# Motor.net
KiCad netlist of a schematic drawn in Altium Designer
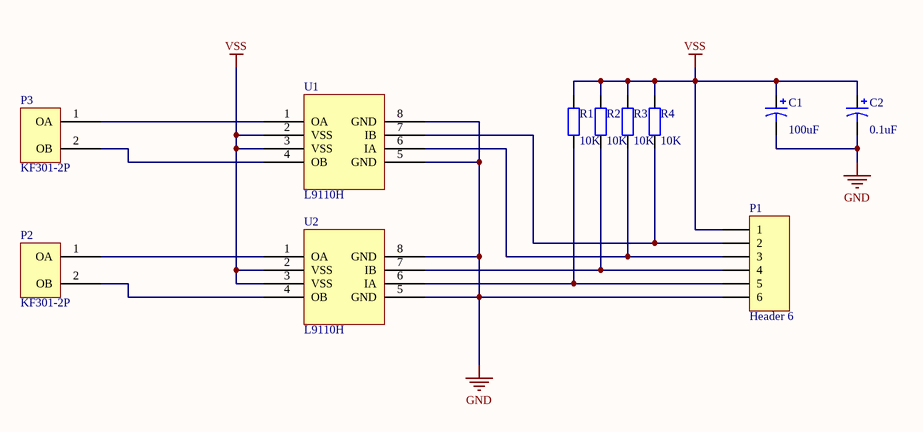
[diagram p0: Motor.SchDoc]

(export (version "E")
  (design (tool "Eeschema 10.0.6"))
  (components
    (comp (ref "C1")
      (value "100uF")
      (footprint "RB7.6-15")
      (description "Polarized Capacitor (Radial)")
      (fields (field (name "Comment") "Cap Pol1") (field (name "PUBLISHER") "Altium Limited"))
      (libsource (lib "Miscellaneous Devices") (part "Cap Pol1"))
    )
    (comp (ref "C2")
      (value "0.1uF")
      (footprint "RB7.6-15")
      (description "Polarized Capacitor (Radial)")
      (fields (field (name "Comment") "Cap Pol1") (field (name "PUBLISHER") "Altium Limited"))
      (libsource (lib "Miscellaneous Devices") (part "Cap Pol1"))
    )
    (comp (ref "P1")
      (value "Header 6")
      (footprint "HDR1X6")
      (description "Header, 6-Pin")
      (fields (field (name "PUBLISHER") "Altium Limited"))
      (libsource (lib "Miscellaneous Connectors") (part "Header 6"))
    )
    (comp (ref "P2") (value "KF301-2P") (footprint "DIP2") (libsource (lib "Motor") (part "KF301-2P")))
    (comp (ref "P3") (value "KF301-2P") (footprint "DIP2") (libsource (lib "Motor") (part "KF301-2P")))
    (comp (ref "R1")
      (value "10K")
      (footprint "AXIAL-0.4")
      (description "Resistor")
      (fields (field (name "Comment") "Res2") (field (name "PUBLISHER") "Altium Limited"))
      (libsource (lib "Miscellaneous Devices") (part "Res2"))
    )
    (comp (ref "R2")
      (value "10K")
      (footprint "AXIAL-0.4")
      (description "Resistor")
      (fields (field (name "Comment") "Res2") (field (name "PUBLISHER") "Altium Limited"))
      (libsource (lib "Miscellaneous Devices") (part "Res2"))
    )
    (comp (ref "R3")
      (value "10K")
      (footprint "AXIAL-0.4")
      (description "Resistor")
      (fields (field (name "Comment") "Res2") (field (name "PUBLISHER") "Altium Limited"))
      (libsource (lib "Miscellaneous Devices") (part "Res2"))
    )
    (comp (ref "R4")
      (value "10K")
      (footprint "AXIAL-0.4")
      (description "Resistor")
      (fields (field (name "Comment") "Res2") (field (name "PUBLISHER") "Altium Limited"))
      (libsource (lib "Miscellaneous Devices") (part "Res2"))
    )
    (comp (ref "U1") (value "L9110H") (footprint "Motor:DIP8") (libsource (lib "Motor") (part "L9110H")))
    (comp (ref "U2") (value "L9110H") (footprint "Motor:DIP8") (libsource (lib "Motor") (part "L9110H")))
  )
  (nets
    (net (code "1") (name "GND") (class "Default")
      (node (ref "C1") (pin "2") (pinfunction "2_2") (pintype "passive"))
      (node (ref "C2") (pin "2") (pinfunction "2_2") (pintype "passive"))
      (node (ref "P1") (pin "6") (pinfunction "6_6") (pintype "passive"))
      (node (ref "U1") (pin "5") (pinfunction "GND_5") (pintype "passive"))
      (node (ref "U1") (pin "8") (pinfunction "GND_8") (pintype "passive"))
      (node (ref "U2") (pin "5") (pinfunction "GND_5") (pintype "passive"))
      (node (ref "U2") (pin "8") (pinfunction "GND_8") (pintype "passive"))
    )
    (net (code "2") (name "Net-(P2-OA)") (class "Default")
      (node (ref "P2") (pin "1") (pinfunction "OA_1") (pintype "passive"))
      (node (ref "U2") (pin "1") (pinfunction "OA_1") (pintype "passive"))
    )
    (net (code "3") (name "Net-(P2-OB)") (class "Default")
      (node (ref "P2") (pin "2") (pinfunction "OB_2") (pintype "passive"))
      (node (ref "U2") (pin "4") (pinfunction "OB_4") (pintype "passive"))
    )
    (net (code "4") (name "Net-(P3-OA)") (class "Default")
      (node (ref "P3") (pin "1") (pinfunction "OA_1") (pintype "passive"))
      (node (ref "U1") (pin "1") (pinfunction "OA_1") (pintype "passive"))
    )
    (net (code "5") (name "Net-(P3-OB)") (class "Default")
      (node (ref "P3") (pin "2") (pinfunction "OB_2") (pintype "passive"))
      (node (ref "U1") (pin "4") (pinfunction "OB_4") (pintype "passive"))
    )
    (net (code "6") (name "Net-(U1-IA)") (class "Default")
      (node (ref "P1") (pin "3") (pinfunction "3_3") (pintype "passive"))
      (node (ref "R3") (pin "1") (pinfunction "1_1") (pintype "passive"))
      (node (ref "U1") (pin "6") (pinfunction "IA_6") (pintype "passive"))
    )
    (net (code "7") (name "Net-(U1-IB)") (class "Default")
      (node (ref "P1") (pin "2") (pinfunction "2_2") (pintype "passive"))
      (node (ref "R4") (pin "1") (pinfunction "1_1") (pintype "passive"))
      (node (ref "U1") (pin "7") (pinfunction "IB_7") (pintype "passive"))
    )
    (net (code "8") (name "Net-(U2-IA)") (class "Default")
      (node (ref "P1") (pin "5") (pinfunction "5_5") (pintype "passive"))
      (node (ref "R1") (pin "1") (pinfunction "1_1") (pintype "passive"))
      (node (ref "U2") (pin "6") (pinfunction "IA_6") (pintype "passive"))
    )
    (net (code "9") (name "Net-(U2-IB)") (class "Default")
      (node (ref "P1") (pin "4") (pinfunction "4_4") (pintype "passive"))
      (node (ref "R2") (pin "1") (pinfunction "1_1") (pintype "passive"))
      (node (ref "U2") (pin "7") (pinfunction "IB_7") (pintype "passive"))
    )
    (net (code "10") (name "VSS") (class "Default")
      (node (ref "C1") (pin "1") (pinfunction "1_1") (pintype "passive"))
      (node (ref "C2") (pin "1") (pinfunction "1_1") (pintype "passive"))
      (node (ref "P1") (pin "1") (pinfunction "1_1") (pintype "passive"))
      (node (ref "R1") (pin "2") (pinfunction "2_2") (pintype "passive"))
      (node (ref "R2") (pin "2") (pinfunction "2_2") (pintype "passive"))
      (node (ref "R3") (pin "2") (pinfunction "2_2") (pintype "passive"))
      (node (ref "R4") (pin "2") (pinfunction "2_2") (pintype "passive"))
      (node (ref "U1") (pin "2") (pinfunction "VSS_2") (pintype "passive"))
      (node (ref "U1") (pin "3") (pinfunction "VSS_3") (pintype "passive"))
      (node (ref "U2") (pin "2") (pinfunction "VSS_2") (pintype "passive"))
      (node (ref "U2") (pin "3") (pinfunction "VSS_3") (pintype "passive"))
    )
  )
)
